# PS3604LRCF.net
KiCad netlist of a schematic drawn in Altium Designer
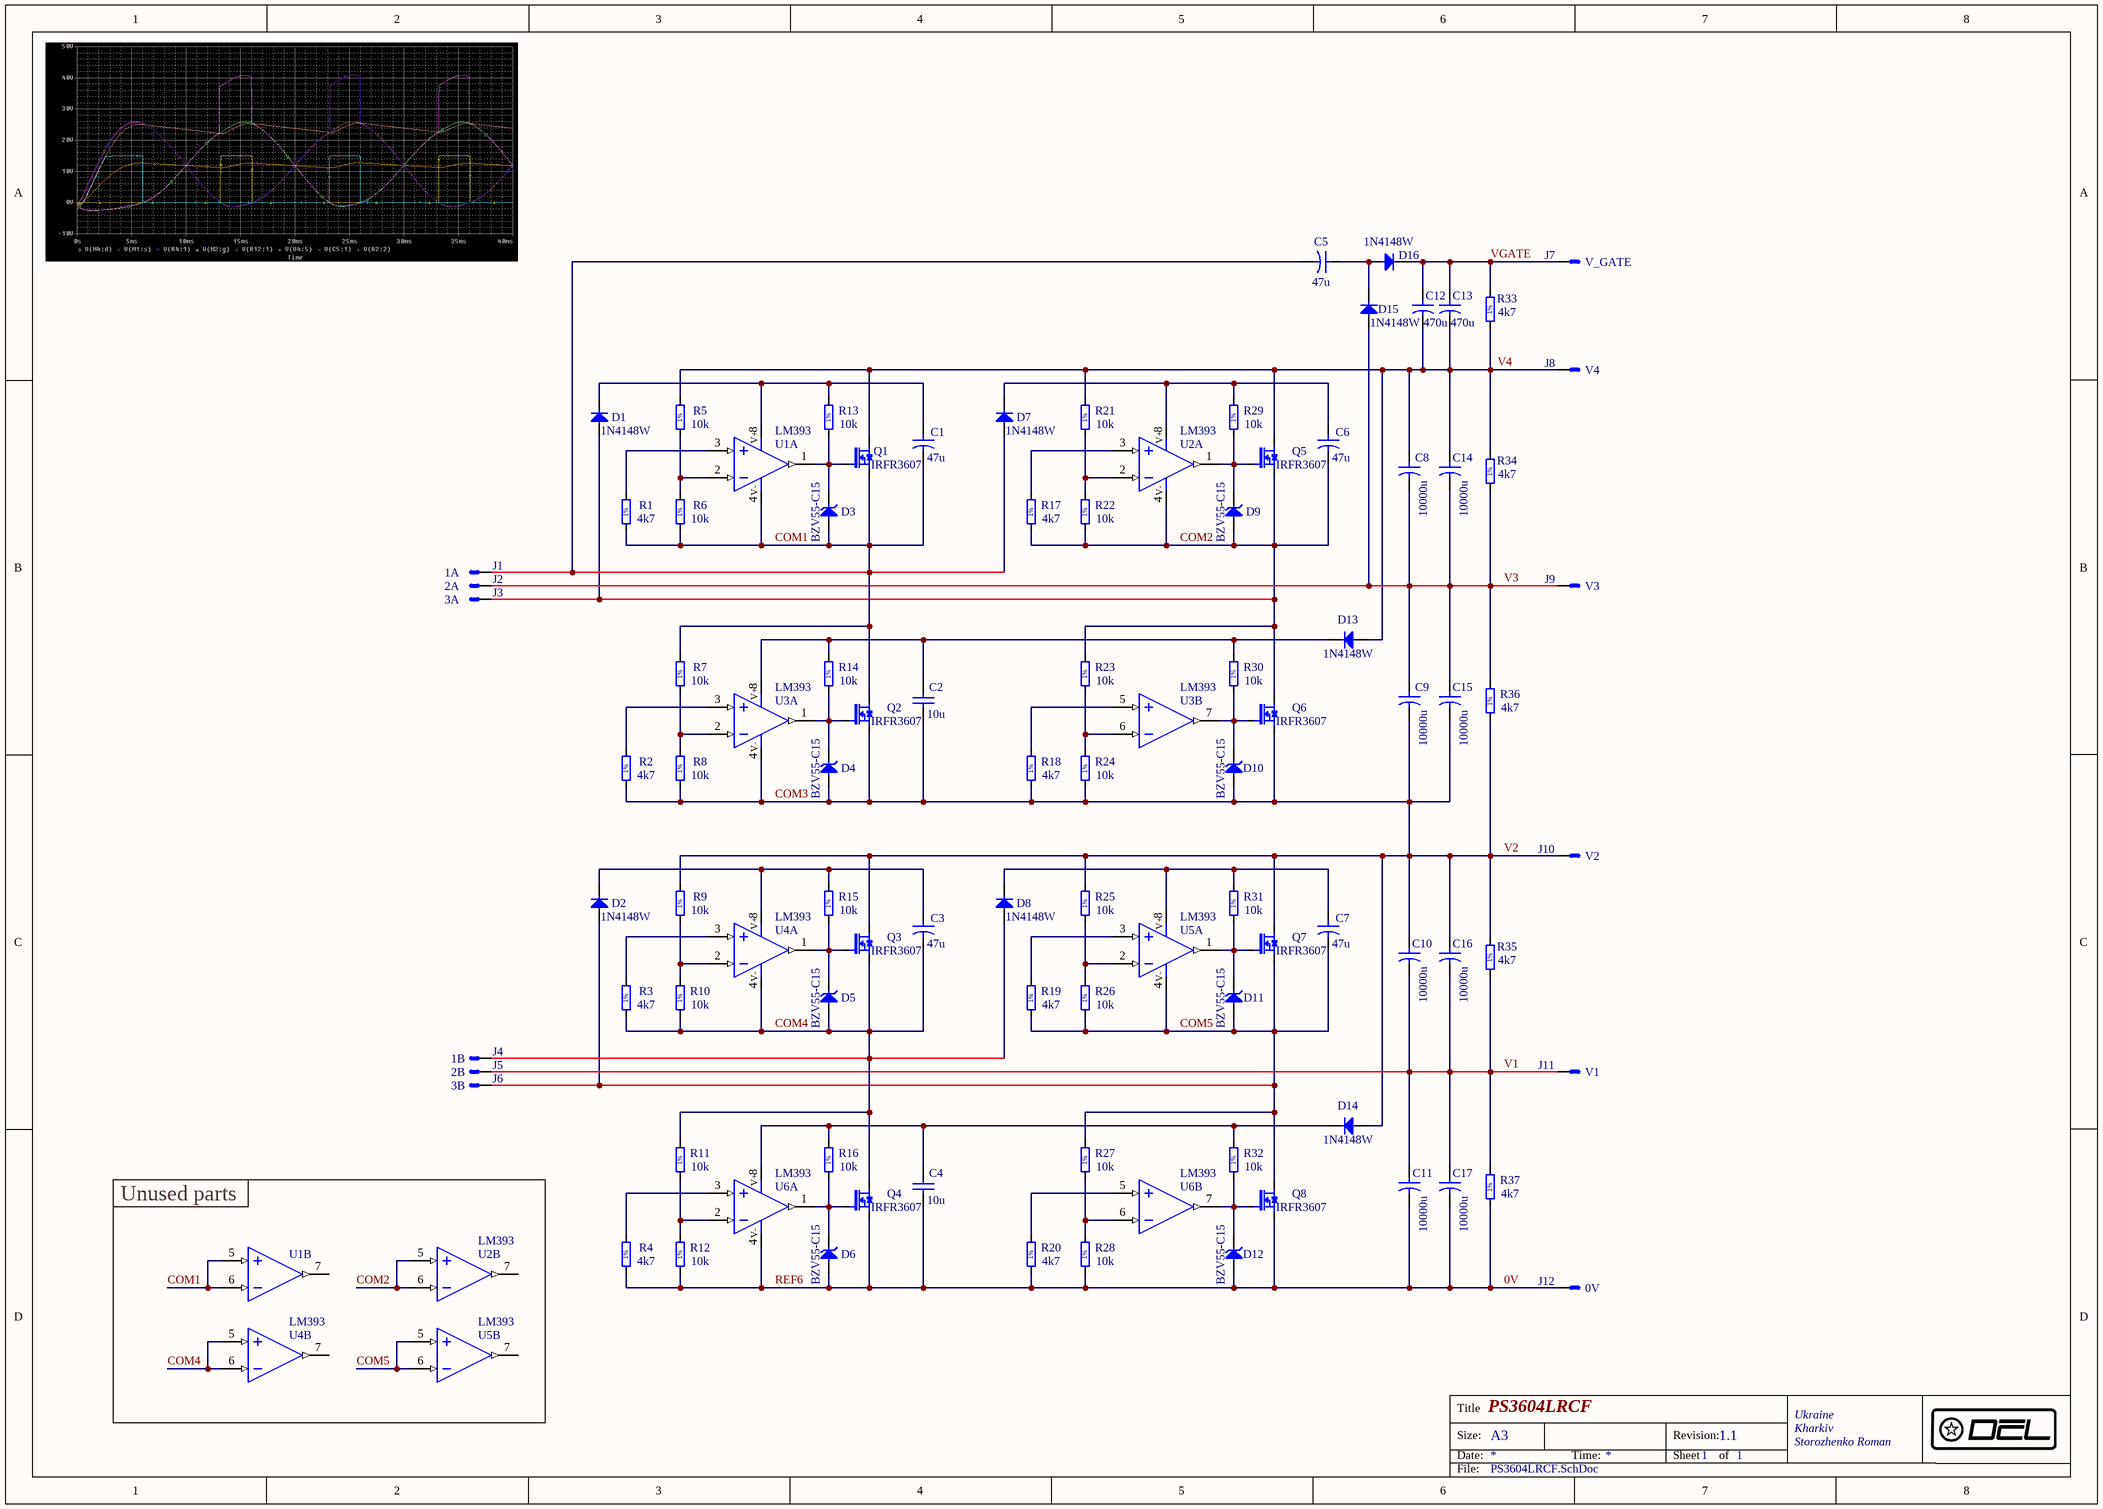
[diagram p0: PS3604LRCF.SchDoc]

(export (version "E")
  (design (tool "Eeschema 10.0.6"))
  (components
    (comp (ref "C1")
      (value "47u")
      (footprint "CAPPR250-630X1120")
      (description "Polarised capacitor")
      (fields
        (field (name "PART NUMBER") "CAER_47UF_50V_20%_EXR470M50B")
        (field (name "VOLTAGE") "50V")
        (field (name "AUTHOR") "DEL")
      )
      (libsource (lib "Capacitors") (part "Capacitor - polarized"))
    )
    (comp (ref "C2")
      (value "10u")
      (footprint "CAPC2012X135N")
      (description "Non-polarised capacitor")
      (fields
        (field (name "PART NUMBER") "CC0805_10UF_16V_10%_X7R")
        (field (name "VOLTAGE") "16V")
        (field (name "AUTHOR") "ELMAN")
      )
      (libsource (lib "Capacitors") (part "Capacitor - non polarized"))
    )
    (comp (ref "C3")
      (value "47u")
      (footprint "CAPPR250-630X1120")
      (description "Polarised capacitor")
      (fields
        (field (name "PART NUMBER") "CAER_47UF_50V_20%_EXR470M50B")
        (field (name "VOLTAGE") "50V")
        (field (name "AUTHOR") "DEL")
      )
      (libsource (lib "Capacitors") (part "Capacitor - polarized"))
    )
    (comp (ref "C4")
      (value "10u")
      (footprint "CAPC2012X135N")
      (description "Non-polarised capacitor")
      (fields
        (field (name "PART NUMBER") "CC0805_10UF_16V_10%_X7R")
        (field (name "VOLTAGE") "16V")
        (field (name "AUTHOR") "ELMAN")
      )
      (libsource (lib "Capacitors") (part "Capacitor - non polarized"))
    )
    (comp (ref "C5")
      (value "47u")
      (footprint "CAPPR250-630X1120")
      (description "Polarised capacitor")
      (fields
        (field (name "PART NUMBER") "CAER_47UF_50V_20%_EXR470M50B")
        (field (name "VOLTAGE") "50V")
        (field (name "AUTHOR") "DEL")
      )
      (libsource (lib "Capacitors") (part "Capacitor - polarized"))
    )
    (comp (ref "C6")
      (value "47u")
      (footprint "CAPPR250-630X1120")
      (description "Polarised capacitor")
      (fields
        (field (name "PART NUMBER") "CAER_47UF_50V_20%_EXR470M50B")
        (field (name "VOLTAGE") "50V")
        (field (name "AUTHOR") "DEL")
      )
      (libsource (lib "Capacitors") (part "Capacitor - polarized"))
    )
    (comp (ref "C7")
      (value "47u")
      (footprint "CAPPR250-630X1120")
      (description "Polarised capacitor")
      (fields
        (field (name "PART NUMBER") "CAER_47UF_50V_20%_EXR470M50B")
        (field (name "VOLTAGE") "50V")
        (field (name "AUTHOR") "DEL")
      )
      (libsource (lib "Capacitors") (part "Capacitor - polarized"))
    )
    (comp (ref "C8")
      (value "10000u")
      (footprint "CAPPR750-1850X3750")
      (description "Polarised capacitor")
      (fields
        (field (name "PART NUMBER") "CAER_10000UF_16V_20%_EXR103M16B")
        (field (name "VOLTAGE") "16V")
        (field (name "AUTHOR") "DEL")
      )
      (libsource (lib "Capacitors") (part "Capacitor - polarized"))
    )
    (comp (ref "C9")
      (value "10000u")
      (footprint "CAPPR750-1850X3750")
      (description "Polarised capacitor")
      (fields
        (field (name "PART NUMBER") "CAER_10000UF_16V_20%_EXR103M16B")
        (field (name "VOLTAGE") "16V")
        (field (name "AUTHOR") "DEL")
      )
      (libsource (lib "Capacitors") (part "Capacitor - polarized"))
    )
    (comp (ref "C10")
      (value "10000u")
      (footprint "CAPPR750-1850X3750")
      (description "Polarised capacitor")
      (fields
        (field (name "PART NUMBER") "CAER_10000UF_16V_20%_EXR103M16B")
        (field (name "VOLTAGE") "16V")
        (field (name "AUTHOR") "DEL")
      )
      (libsource (lib "Capacitors") (part "Capacitor - polarized"))
    )
    (comp (ref "C11")
      (value "10000u")
      (footprint "CAPPR750-1850X3750")
      (description "Polarised capacitor")
      (fields
        (field (name "PART NUMBER") "CAER_10000UF_16V_20%_EXR103M16B")
        (field (name "VOLTAGE") "16V")
        (field (name "AUTHOR") "DEL")
      )
      (libsource (lib "Capacitors") (part "Capacitor - polarized"))
    )
    (comp (ref "C12")
      (value "470u")
      (footprint "CAPPR500-1050X2200")
      (description "Polarised capacitor")
      (fields
        (field (name "PART NUMBER") "CAER_470UF_35V_20%_EXR471M35B")
        (field (name "VOLTAGE") "36V")
        (field (name "AUTHOR") "DEL")
      )
      (libsource (lib "Capacitors") (part "Capacitor - polarized"))
    )
    (comp (ref "C13")
      (value "470u")
      (footprint "CAPPR500-1050X2200")
      (description "Polarised capacitor")
      (fields
        (field (name "PART NUMBER") "CAER_470UF_35V_20%_EXR471M35B")
        (field (name "VOLTAGE") "36V")
        (field (name "AUTHOR") "DEL")
      )
      (libsource (lib "Capacitors") (part "Capacitor - polarized"))
    )
    (comp (ref "C14")
      (value "10000u")
      (footprint "CAPPR750-1850X3750")
      (description "Polarised capacitor")
      (fields
        (field (name "PART NUMBER") "CAER_10000UF_16V_20%_EXR103M16B")
        (field (name "VOLTAGE") "16V")
        (field (name "AUTHOR") "DEL")
      )
      (libsource (lib "Capacitors") (part "Capacitor - polarized"))
    )
    (comp (ref "C15")
      (value "10000u")
      (footprint "CAPPR750-1850X3750")
      (description "Polarised capacitor")
      (fields
        (field (name "PART NUMBER") "CAER_10000UF_16V_20%_EXR103M16B")
        (field (name "VOLTAGE") "16V")
        (field (name "AUTHOR") "DEL")
      )
      (libsource (lib "Capacitors") (part "Capacitor - polarized"))
    )
    (comp (ref "C16")
      (value "10000u")
      (footprint "CAPPR750-1850X3750")
      (description "Polarised capacitor")
      (fields
        (field (name "PART NUMBER") "CAER_10000UF_16V_20%_EXR103M16B")
        (field (name "VOLTAGE") "16V")
        (field (name "AUTHOR") "DEL")
      )
      (libsource (lib "Capacitors") (part "Capacitor - polarized"))
    )
    (comp (ref "C17")
      (value "10000u")
      (footprint "CAPPR750-1850X3750")
      (description "Polarised capacitor")
      (fields
        (field (name "PART NUMBER") "CAER_10000UF_16V_20%_EXR103M16B")
        (field (name "VOLTAGE") "16V")
        (field (name "AUTHOR") "DEL")
      )
      (libsource (lib "Capacitors") (part "Capacitor - polarized"))
    )
    (comp (ref "D1")
      (value "1N4148W")
      (footprint "SOD3715X145N")
      (description "Diode")
      (fields (field (name "VOLTAGE") "75V") (field (name "POWER") "150mA") (field (name "AUTHOR") "DEL"))
      (libsource (lib "ICs And Semiconductors") (part "Diode"))
    )
    (comp (ref "D2")
      (value "1N4148W")
      (footprint "SOD3715X145N")
      (description "Diode")
      (fields (field (name "VOLTAGE") "75V") (field (name "POWER") "150mA") (field (name "AUTHOR") "DEL"))
      (libsource (lib "ICs And Semiconductors") (part "Diode"))
    )
    (comp (ref "D3")
      (value "BZV55-C15")
      (footprint "DIOMELF3515N")
      (description "Zener Diode")
      (fields
        (field (name "VOLTAGE") "15V")
        (field (name "POWER") "500mW")
        (field (name "AUTHOR") "CERN DEM JLC")
      )
      (libsource (lib "ICs And Semiconductors") (part "Diode Zener"))
    )
    (comp (ref "D4")
      (value "BZV55-C15")
      (footprint "DIOMELF3515N")
      (description "Zener Diode")
      (fields
        (field (name "VOLTAGE") "15V")
        (field (name "POWER") "500mW")
        (field (name "AUTHOR") "CERN DEM JLC")
      )
      (libsource (lib "ICs And Semiconductors") (part "Diode Zener"))
    )
    (comp (ref "D5")
      (value "BZV55-C15")
      (footprint "DIOMELF3515N")
      (description "Zener Diode")
      (fields
        (field (name "VOLTAGE") "15V")
        (field (name "POWER") "500mW")
        (field (name "AUTHOR") "CERN DEM JLC")
      )
      (libsource (lib "ICs And Semiconductors") (part "Diode Zener"))
    )
    (comp (ref "D6")
      (value "BZV55-C15")
      (footprint "DIOMELF3515N")
      (description "Zener Diode")
      (fields
        (field (name "VOLTAGE") "15V")
        (field (name "POWER") "500mW")
        (field (name "AUTHOR") "CERN DEM JLC")
      )
      (libsource (lib "ICs And Semiconductors") (part "Diode Zener"))
    )
    (comp (ref "D7")
      (value "1N4148W")
      (footprint "SOD3715X145N")
      (description "Diode")
      (fields (field (name "VOLTAGE") "75V") (field (name "POWER") "150mA") (field (name "AUTHOR") "DEL"))
      (libsource (lib "ICs And Semiconductors") (part "Diode"))
    )
    (comp (ref "D8")
      (value "1N4148W")
      (footprint "SOD3715X145N")
      (description "Diode")
      (fields (field (name "VOLTAGE") "75V") (field (name "POWER") "150mA") (field (name "AUTHOR") "DEL"))
      (libsource (lib "ICs And Semiconductors") (part "Diode"))
    )
    (comp (ref "D9")
      (value "BZV55-C15")
      (footprint "DIOMELF3515N")
      (description "Zener Diode")
      (fields
        (field (name "VOLTAGE") "15V")
        (field (name "POWER") "500mW")
        (field (name "AUTHOR") "CERN DEM JLC")
      )
      (libsource (lib "ICs And Semiconductors") (part "Diode Zener"))
    )
    (comp (ref "D10")
      (value "BZV55-C15")
      (footprint "DIOMELF3515N")
      (description "Zener Diode")
      (fields
        (field (name "VOLTAGE") "15V")
        (field (name "POWER") "500mW")
        (field (name "AUTHOR") "CERN DEM JLC")
      )
      (libsource (lib "ICs And Semiconductors") (part "Diode Zener"))
    )
    (comp (ref "D11")
      (value "BZV55-C15")
      (footprint "DIOMELF3515N")
      (description "Zener Diode")
      (fields
        (field (name "VOLTAGE") "15V")
        (field (name "POWER") "500mW")
        (field (name "AUTHOR") "CERN DEM JLC")
      )
      (libsource (lib "ICs And Semiconductors") (part "Diode Zener"))
    )
    (comp (ref "D12")
      (value "BZV55-C15")
      (footprint "DIOMELF3515N")
      (description "Zener Diode")
      (fields
        (field (name "VOLTAGE") "15V")
        (field (name "POWER") "500mW")
        (field (name "AUTHOR") "CERN DEM JLC")
      )
      (libsource (lib "ICs And Semiconductors") (part "Diode Zener"))
    )
    (comp (ref "D13")
      (value "1N4148W")
      (footprint "SOD3715X145N")
      (description "Diode")
      (fields (field (name "VOLTAGE") "75V") (field (name "POWER") "150mA") (field (name "AUTHOR") "DEL"))
      (libsource (lib "ICs And Semiconductors") (part "Diode"))
    )
    (comp (ref "D14")
      (value "1N4148W")
      (footprint "SOD3715X145N")
      (description "Diode")
      (fields (field (name "VOLTAGE") "75V") (field (name "POWER") "150mA") (field (name "AUTHOR") "DEL"))
      (libsource (lib "ICs And Semiconductors") (part "Diode"))
    )
    (comp (ref "D15")
      (value "1N4148W")
      (footprint "SOD3715X145N")
      (description "Diode")
      (fields (field (name "VOLTAGE") "75V") (field (name "POWER") "150mA") (field (name "AUTHOR") "DEL"))
      (libsource (lib "ICs And Semiconductors") (part "Diode"))
    )
    (comp (ref "D16")
      (value "1N4148W")
      (footprint "SOD3715X145N")
      (description "Diode")
      (fields (field (name "VOLTAGE") "75V") (field (name "POWER") "150mA") (field (name "AUTHOR") "DEL"))
      (libsource (lib "ICs And Semiconductors") (part "Diode"))
    )
    (comp (ref "J1")
      (value "Quixon™")
      (footprint "MOLEX_19_70_54203")
      (description "Single Pin Male")
      (fields
        (field (name "PART NUMBER") "MOLEX_19_70_54203")
        (field (name "MANUFACTURER") "MOLEX")
        (field (name "AUTHOR") "DEL")
      )
      (libsource (lib "Connectors") (part "Single Pin Male"))
    )
    (comp (ref "J2")
      (value "Quixon™")
      (footprint "MOLEX_19_70_54203")
      (description "Single Pin Male")
      (fields
        (field (name "PART NUMBER") "MOLEX_19_70_54203")
        (field (name "MANUFACTURER") "MOLEX")
        (field (name "AUTHOR") "DEL")
      )
      (libsource (lib "Connectors") (part "Single Pin Male"))
    )
    (comp (ref "J3")
      (value "Quixon™")
      (footprint "MOLEX_19_70_54203")
      (description "Single Pin Male")
      (fields
        (field (name "PART NUMBER") "MOLEX_19_70_54203")
        (field (name "MANUFACTURER") "MOLEX")
        (field (name "AUTHOR") "DEL")
      )
      (libsource (lib "Connectors") (part "Single Pin Male"))
    )
    (comp (ref "J4")
      (value "Quixon™")
      (footprint "MOLEX_19_70_54203")
      (description "Single Pin Male")
      (fields
        (field (name "PART NUMBER") "MOLEX_19_70_54203")
        (field (name "MANUFACTURER") "MOLEX")
        (field (name "AUTHOR") "DEL")
      )
      (libsource (lib "Connectors") (part "Single Pin Male"))
    )
    (comp (ref "J5")
      (value "Quixon™")
      (footprint "MOLEX_19_70_54203")
      (description "Single Pin Male")
      (fields
        (field (name "PART NUMBER") "MOLEX_19_70_54203")
        (field (name "MANUFACTURER") "MOLEX")
        (field (name "AUTHOR") "DEL")
      )
      (libsource (lib "Connectors") (part "Single Pin Male"))
    )
    (comp (ref "J6")
      (value "Quixon™")
      (footprint "MOLEX_19_70_54203")
      (description "Single Pin Male")
      (fields
        (field (name "PART NUMBER") "MOLEX_19_70_54203")
        (field (name "MANUFACTURER") "MOLEX")
        (field (name "AUTHOR") "DEL")
      )
      (libsource (lib "Connectors") (part "Single Pin Male"))
    )
    (comp (ref "J7")
      (value "Quixon™")
      (footprint "MOLEX_19_70_54203")
      (description "Single Pin Male")
      (fields
        (field (name "PART NUMBER") "MOLEX_19_70_54203")
        (field (name "MANUFACTURER") "MOLEX")
        (field (name "AUTHOR") "DEL")
      )
      (libsource (lib "Connectors") (part "Single Pin Male"))
    )
    (comp (ref "J8")
      (value "Quixon™")
      (footprint "MOLEX_19_70_54203")
      (description "Single Pin Male")
      (fields
        (field (name "PART NUMBER") "MOLEX_19_70_54203")
        (field (name "MANUFACTURER") "MOLEX")
        (field (name "AUTHOR") "DEL")
      )
      (libsource (lib "Connectors") (part "Single Pin Male"))
    )
    (comp (ref "J9")
      (value "Quixon™")
      (footprint "MOLEX_19_70_54203")
      (description "Single Pin Male")
      (fields
        (field (name "PART NUMBER") "MOLEX_19_70_54203")
        (field (name "MANUFACTURER") "MOLEX")
        (field (name "AUTHOR") "DEL")
      )
      (libsource (lib "Connectors") (part "Single Pin Male"))
    )
    (comp (ref "J10")
      (value "Quixon™")
      (footprint "MOLEX_19_70_54203")
      (description "Single Pin Male")
      (fields
        (field (name "PART NUMBER") "MOLEX_19_70_54203")
        (field (name "MANUFACTURER") "MOLEX")
        (field (name "AUTHOR") "DEL")
      )
      (libsource (lib "Connectors") (part "Single Pin Male"))
    )
    (comp (ref "J11")
      (value "Quixon™")
      (footprint "MOLEX_19_70_54203")
      (description "Single Pin Male")
      (fields
        (field (name "PART NUMBER") "MOLEX_19_70_54203")
        (field (name "MANUFACTURER") "MOLEX")
        (field (name "AUTHOR") "DEL")
      )
      (libsource (lib "Connectors") (part "Single Pin Male"))
    )
    (comp (ref "J12")
      (value "Quixon™")
      (footprint "MOLEX_19_70_54203")
      (description "Single Pin Male")
      (fields
        (field (name "PART NUMBER") "MOLEX_19_70_54203")
        (field (name "MANUFACTURER") "MOLEX")
        (field (name "AUTHOR") "DEL")
      )
      (libsource (lib "Connectors") (part "Single Pin Male"))
    )
    (comp (ref "Q1")
      (value "IRFR3607")
      (footprint "TO228P991X239-3N-R546X521")
      (description "N-CHANNEL MOSFET WITH DIODE")
      (fields
        (field (name "PART NUMBER") "IRFR3607PbF")
        (field (name "MANUFACTURER") "INTERNATIONAL RECTIFIER")
        (field (name "AUTHOR") "DEL")
      )
      (libsource (lib "ICs And Semiconductors") (part "N-MOSFET-D 1G 2S 3D"))
    )
    (comp (ref "Q2")
      (value "IRFR3607")
      (footprint "TO228P991X239-3N-R546X521")
      (description "N-CHANNEL MOSFET WITH DIODE")
      (fields
        (field (name "PART NUMBER") "IRFR3607PbF")
        (field (name "MANUFACTURER") "INTERNATIONAL RECTIFIER")
        (field (name "AUTHOR") "DEL")
      )
      (libsource (lib "ICs And Semiconductors") (part "N-MOSFET-D 1G 2S 3D"))
    )
    (comp (ref "Q3")
      (value "IRFR3607")
      (footprint "TO228P991X239-3N-R546X521")
      (description "N-CHANNEL MOSFET WITH DIODE")
      (fields
        (field (name "PART NUMBER") "IRFR3607PbF")
        (field (name "MANUFACTURER") "INTERNATIONAL RECTIFIER")
        (field (name "AUTHOR") "DEL")
      )
      (libsource (lib "ICs And Semiconductors") (part "N-MOSFET-D 1G 2S 3D"))
    )
    (comp (ref "Q4")
      (value "IRFR3607")
      (footprint "TO228P991X239-3N-R546X521")
      (description "N-CHANNEL MOSFET WITH DIODE")
      (fields
        (field (name "PART NUMBER") "IRFR3607PbF")
        (field (name "MANUFACTURER") "INTERNATIONAL RECTIFIER")
        (field (name "AUTHOR") "DEL")
      )
      (libsource (lib "ICs And Semiconductors") (part "N-MOSFET-D 1G 2S 3D"))
    )
    (comp (ref "Q5")
      (value "IRFR3607")
      (footprint "TO228P991X239-3N-R546X521")
      (description "N-CHANNEL MOSFET WITH DIODE")
      (fields
        (field (name "PART NUMBER") "IRFR3607PbF")
        (field (name "MANUFACTURER") "INTERNATIONAL RECTIFIER")
        (field (name "AUTHOR") "DEL")
      )
      (libsource (lib "ICs And Semiconductors") (part "N-MOSFET-D 1G 2S 3D"))
    )
    (comp (ref "Q6")
      (value "IRFR3607")
      (footprint "TO228P991X239-3N-R546X521")
      (description "N-CHANNEL MOSFET WITH DIODE")
      (fields
        (field (name "PART NUMBER") "IRFR3607PbF")
        (field (name "MANUFACTURER") "INTERNATIONAL RECTIFIER")
        (field (name "AUTHOR") "DEL")
      )
      (libsource (lib "ICs And Semiconductors") (part "N-MOSFET-D 1G 2S 3D"))
    )
    (comp (ref "Q7")
      (value "IRFR3607")
      (footprint "TO228P991X239-3N-R546X521")
      (description "N-CHANNEL MOSFET WITH DIODE")
      (fields
        (field (name "PART NUMBER") "IRFR3607PbF")
        (field (name "MANUFACTURER") "INTERNATIONAL RECTIFIER")
        (field (name "AUTHOR") "DEL")
      )
      (libsource (lib "ICs And Semiconductors") (part "N-MOSFET-D 1G 2S 3D"))
    )
    (comp (ref "Q8")
      (value "IRFR3607")
      (footprint "TO228P991X239-3N-R546X521")
      (description "N-CHANNEL MOSFET WITH DIODE")
      (fields
        (field (name "PART NUMBER") "IRFR3607PbF")
        (field (name "MANUFACTURER") "INTERNATIONAL RECTIFIER")
        (field (name "AUTHOR") "DEL")
      )
      (libsource (lib "ICs And Semiconductors") (part "N-MOSFET-D 1G 2S 3D"))
    )
    (comp (ref "R1")
      (value "4k7")
      (footprint "RESC1608X55N")
      (description "Resistor - 1%")
      (fields
        (field (name "PART NUMBER") "R0603_4K7_1%_0.1W_100PPM")
        (field (name "POWER") "0.1W")
        (field (name "AUTHOR") "CERN DEM JLC")
      )
      (libsource (lib "Resistors") (part "Resistor - 1%"))
    )
    (comp (ref "R2")
      (value "4k7")
      (footprint "RESC1608X55N")
      (description "Resistor - 1%")
      (fields
        (field (name "PART NUMBER") "R0603_4K7_1%_0.1W_100PPM")
        (field (name "POWER") "0.1W")
        (field (name "AUTHOR") "CERN DEM JLC")
      )
      (libsource (lib "Resistors") (part "Resistor - 1%"))
    )
    (comp (ref "R3")
      (value "4k7")
      (footprint "RESC1608X55N")
      (description "Resistor - 1%")
      (fields
        (field (name "PART NUMBER") "R0603_4K7_1%_0.1W_100PPM")
        (field (name "POWER") "0.1W")
        (field (name "AUTHOR") "CERN DEM JLC")
      )
      (libsource (lib "Resistors") (part "Resistor - 1%"))
    )
    (comp (ref "R4")
      (value "4k7")
      (footprint "RESC1608X55N")
      (description "Resistor - 1%")
      (fields
        (field (name "PART NUMBER") "R0603_4K7_1%_0.1W_100PPM")
        (field (name "POWER") "0.1W")
        (field (name "AUTHOR") "CERN DEM JLC")
      )
      (libsource (lib "Resistors") (part "Resistor - 1%"))
    )
    (comp (ref "R5")
      (value "10k")
      (footprint "RESC1608X55N")
      (description "Resistor - 1%")
      (fields
        (field (name "PART NUMBER") "R0603_10K_1%_0.1W_100PPM")
        (field (name "POWER") "0.1W")
        (field (name "AUTHOR") "CERN DEM JLC")
      )
      (libsource (lib "Resistors") (part "Resistor - 1%"))
    )
    (comp (ref "R6")
      (value "10k")
      (footprint "RESC1608X55N")
      (description "Resistor - 1%")
      (fields
        (field (name "PART NUMBER") "R0603_10K_1%_0.1W_100PPM")
        (field (name "POWER") "0.1W")
        (field (name "AUTHOR") "CERN DEM JLC")
      )
      (libsource (lib "Resistors") (part "Resistor - 1%"))
    )
    (comp (ref "R7")
      (value "10k")
      (footprint "RESC1608X55N")
      (description "Resistor - 1%")
      (fields
        (field (name "PART NUMBER") "R0603_10K_1%_0.1W_100PPM")
        (field (name "POWER") "0.1W")
        (field (name "AUTHOR") "CERN DEM JLC")
      )
      (libsource (lib "Resistors") (part "Resistor - 1%"))
    )
    (comp (ref "R8")
      (value "10k")
      (footprint "RESC1608X55N")
      (description "Resistor - 1%")
      (fields
        (field (name "PART NUMBER") "R0603_10K_1%_0.1W_100PPM")
        (field (name "POWER") "0.1W")
        (field (name "AUTHOR") "CERN DEM JLC")
      )
      (libsource (lib "Resistors") (part "Resistor - 1%"))
    )
    (comp (ref "R9")
      (value "10k")
      (footprint "RESC1608X55N")
      (description "Resistor - 1%")
      (fields
        (field (name "PART NUMBER") "R0603_10K_1%_0.1W_100PPM")
        (field (name "POWER") "0.1W")
        (field (name "AUTHOR") "CERN DEM JLC")
      )
      (libsource (lib "Resistors") (part "Resistor - 1%"))
    )
    (comp (ref "R10")
      (value "10k")
      (footprint "RESC1608X55N")
      (description "Resistor - 1%")
      (fields
        (field (name "PART NUMBER") "R0603_10K_1%_0.1W_100PPM")
        (field (name "POWER") "0.1W")
        (field (name "AUTHOR") "CERN DEM JLC")
      )
      (libsource (lib "Resistors") (part "Resistor - 1%"))
    )
    (comp (ref "R11")
      (value "10k")
      (footprint "RESC1608X55N")
      (description "Resistor - 1%")
      (fields
        (field (name "PART NUMBER") "R0603_10K_1%_0.1W_100PPM")
        (field (name "POWER") "0.1W")
        (field (name "AUTHOR") "CERN DEM JLC")
      )
      (libsource (lib "Resistors") (part "Resistor - 1%"))
    )
    (comp (ref "R12")
      (value "10k")
      (footprint "RESC1608X55N")
      (description "Resistor - 1%")
      (fields
        (field (name "PART NUMBER") "R0603_10K_1%_0.1W_100PPM")
        (field (name "POWER") "0.1W")
        (field (name "AUTHOR") "CERN DEM JLC")
      )
      (libsource (lib "Resistors") (part "Resistor - 1%"))
    )
    (comp (ref "R13")
      (value "10k")
      (footprint "RESC1608X55N")
      (description "Resistor - 1%")
      (fields
        (field (name "PART NUMBER") "R0603_10K_1%_0.1W_100PPM")
        (field (name "POWER") "0.1W")
        (field (name "AUTHOR") "CERN DEM JLC")
      )
      (libsource (lib "Resistors") (part "Resistor - 1%"))
    )
    (comp (ref "R14")
      (value "10k")
      (footprint "RESC1608X55N")
      (description "Resistor - 1%")
      (fields
        (field (name "PART NUMBER") "R0603_10K_1%_0.1W_100PPM")
        (field (name "POWER") "0.1W")
        (field (name "AUTHOR") "CERN DEM JLC")
      )
      (libsource (lib "Resistors") (part "Resistor - 1%"))
    )
    (comp (ref "R15")
      (value "10k")
      (footprint "RESC1608X55N")
      (description "Resistor - 1%")
      (fields
        (field (name "PART NUMBER") "R0603_10K_1%_0.1W_100PPM")
        (field (name "POWER") "0.1W")
        (field (name "AUTHOR") "CERN DEM JLC")
      )
      (libsource (lib "Resistors") (part "Resistor - 1%"))
    )
    (comp (ref "R16")
      (value "10k")
      (footprint "RESC1608X55N")
      (description "Resistor - 1%")
      (fields
        (field (name "PART NUMBER") "R0603_10K_1%_0.1W_100PPM")
        (field (name "POWER") "0.1W")
        (field (name "AUTHOR") "CERN DEM JLC")
      )
      (libsource (lib "Resistors") (part "Resistor - 1%"))
    )
    (comp (ref "R17")
      (value "4k7")
      (footprint "RESC1608X55N")
      (description "Resistor - 1%")
      (fields
        (field (name "PART NUMBER") "R0603_4K7_1%_0.1W_100PPM")
        (field (name "POWER") "0.1W")
        (field (name "AUTHOR") "CERN DEM JLC")
      )
      (libsource (lib "Resistors") (part "Resistor - 1%"))
    )
    (comp (ref "R18")
      (value "4k7")
      (footprint "RESC1608X55N")
      (description "Resistor - 1%")
      (fields
        (field (name "PART NUMBER") "R0603_4K7_1%_0.1W_100PPM")
        (field (name "POWER") "0.1W")
        (field (name "AUTHOR") "CERN DEM JLC")
      )
      (libsource (lib "Resistors") (part "Resistor - 1%"))
    )
    (comp (ref "R19")
      (value "4k7")
      (footprint "RESC1608X55N")
      (description "Resistor - 1%")
      (fields
        (field (name "PART NUMBER") "R0603_4K7_1%_0.1W_100PPM")
        (field (name "POWER") "0.1W")
        (field (name "AUTHOR") "CERN DEM JLC")
      )
      (libsource (lib "Resistors") (part "Resistor - 1%"))
    )
    (comp (ref "R20")
      (value "4k7")
      (footprint "RESC1608X55N")
      (description "Resistor - 1%")
      (fields
        (field (name "PART NUMBER") "R0603_4K7_1%_0.1W_100PPM")
        (field (name "POWER") "0.1W")
        (field (name "AUTHOR") "CERN DEM JLC")
      )
      (libsource (lib "Resistors") (part "Resistor - 1%"))
    )
    (comp (ref "R21")
      (value "10k")
      (footprint "RESC1608X55N")
      (description "Resistor - 1%")
      (fields
        (field (name "PART NUMBER") "R0603_10K_1%_0.1W_100PPM")
        (field (name "POWER") "0.1W")
        (field (name "AUTHOR") "CERN DEM JLC")
      )
      (libsource (lib "Resistors") (part "Resistor - 1%"))
    )
    (comp (ref "R22")
      (value "10k")
      (footprint "RESC1608X55N")
      (description "Resistor - 1%")
      (fields
        (field (name "PART NUMBER") "R0603_10K_1%_0.1W_100PPM")
        (field (name "POWER") "0.1W")
        (field (name "AUTHOR") "CERN DEM JLC")
      )
      (libsource (lib "Resistors") (part "Resistor - 1%"))
    )
    (comp (ref "R23")
      (value "10k")
      (footprint "RESC1608X55N")
      (description "Resistor - 1%")
      (fields
        (field (name "PART NUMBER") "R0603_10K_1%_0.1W_100PPM")
        (field (name "POWER") "0.1W")
        (field (name "AUTHOR") "CERN DEM JLC")
      )
      (libsource (lib "Resistors") (part "Resistor - 1%"))
    )
    (comp (ref "R24")
      (value "10k")
      (footprint "RESC1608X55N")
      (description "Resistor - 1%")
      (fields
        (field (name "PART NUMBER") "R0603_10K_1%_0.1W_100PPM")
        (field (name "POWER") "0.1W")
        (field (name "AUTHOR") "CERN DEM JLC")
      )
      (libsource (lib "Resistors") (part "Resistor - 1%"))
    )
    (comp (ref "R25")
      (value "10k")
      (footprint "RESC1608X55N")
      (description "Resistor - 1%")
      (fields
        (field (name "PART NUMBER") "R0603_10K_1%_0.1W_100PPM")
        (field (name "POWER") "0.1W")
        (field (name "AUTHOR") "CERN DEM JLC")
      )
      (libsource (lib "Resistors") (part "Resistor - 1%"))
    )
    (comp (ref "R26")
      (value "10k")
      (footprint "RESC1608X55N")
      (description "Resistor - 1%")
      (fields
        (field (name "PART NUMBER") "R0603_10K_1%_0.1W_100PPM")
        (field (name "POWER") "0.1W")
        (field (name "AUTHOR") "CERN DEM JLC")
      )
      (libsource (lib "Resistors") (part "Resistor - 1%"))
    )
    (comp (ref "R27")
      (value "10k")
      (footprint "RESC1608X55N")
      (description "Resistor - 1%")
      (fields
        (field (name "PART NUMBER") "R0603_10K_1%_0.1W_100PPM")
        (field (name "POWER") "0.1W")
        (field (name "AUTHOR") "CERN DEM JLC")
      )
      (libsource (lib "Resistors") (part "Resistor - 1%"))
    )
    (comp (ref "R28")
      (value "10k")
      (footprint "RESC1608X55N")
      (description "Resistor - 1%")
      (fields
        (field (name "PART NUMBER") "R0603_10K_1%_0.1W_100PPM")
        (field (name "POWER") "0.1W")
        (field (name "AUTHOR") "CERN DEM JLC")
      )
      (libsource (lib "Resistors") (part "Resistor - 1%"))
    )
    (comp (ref "R29")
      (value "10k")
      (footprint "RESC1608X55N")
      (description "Resistor - 1%")
      (fields
        (field (name "PART NUMBER") "R0603_10K_1%_0.1W_100PPM")
        (field (name "POWER") "0.1W")
        (field (name "AUTHOR") "CERN DEM JLC")
      )
      (libsource (lib "Resistors") (part "Resistor - 1%"))
    )
    (comp (ref "R30")
      (value "10k")
      (footprint "RESC1608X55N")
      (description "Resistor - 1%")
      (fields
        (field (name "PART NUMBER") "R0603_10K_1%_0.1W_100PPM")
        (field (name "POWER") "0.1W")
        (field (name "AUTHOR") "CERN DEM JLC")
      )
      (libsource (lib "Resistors") (part "Resistor - 1%"))
    )
    (comp (ref "R31")
      (value "10k")
      (footprint "RESC1608X55N")
      (description "Resistor - 1%")
      (fields
        (field (name "PART NUMBER") "R0603_10K_1%_0.1W_100PPM")
        (field (name "POWER") "0.1W")
        (field (name "AUTHOR") "CERN DEM JLC")
      )
      (libsource (lib "Resistors") (part "Resistor - 1%"))
    )
    (comp (ref "R32")
      (value "10k")
      (footprint "RESC1608X55N")
      (description "Resistor - 1%")
      (fields
        (field (name "PART NUMBER") "R0603_10K_1%_0.1W_100PPM")
        (field (name "POWER") "0.1W")
        (field (name "AUTHOR") "CERN DEM JLC")
      )
      (libsource (lib "Resistors") (part "Resistor - 1%"))
    )
    (comp (ref "R33")
      (value "4k7")
      (footprint "RESC1608X55N")
      (description "Resistor - 1%")
      (fields
        (field (name "PART NUMBER") "R0603_4K7_1%_0.1W_100PPM")
        (field (name "POWER") "0.1W")
        (field (name "AUTHOR") "CERN DEM JLC")
      )
      (libsource (lib "Resistors") (part "Resistor - 1%"))
    )
    (comp (ref "R34")
      (value "4k7")
      (footprint "RESC1608X55N")
      (description "Resistor - 1%")
      (fields
        (field (name "PART NUMBER") "R0603_4K7_1%_0.1W_100PPM")
        (field (name "POWER") "0.1W")
        (field (name "AUTHOR") "CERN DEM JLC")
      )
      (libsource (lib "Resistors") (part "Resistor - 1%"))
    )
    (comp (ref "R35")
      (value "4k7")
      (footprint "RESC1608X55N")
      (description "Resistor - 1%")
      (fields
        (field (name "PART NUMBER") "R0603_4K7_1%_0.1W_100PPM")
        (field (name "POWER") "0.1W")
        (field (name "AUTHOR") "CERN DEM JLC")
      )
      (libsource (lib "Resistors") (part "Resistor - 1%"))
    )
    (comp (ref "R36")
      (value "4k7")
      (footprint "RESC1608X55N")
      (description "Resistor - 1%")
      (fields
        (field (name "PART NUMBER") "R0603_4K7_1%_0.1W_100PPM")
        (field (name "POWER") "0.1W")
        (field (name "AUTHOR") "CERN DEM JLC")
      )
      (libsource (lib "Resistors") (part "Resistor - 1%"))
    )
    (comp (ref "R37")
      (value "4k7")
      (footprint "RESC1608X55N")
      (description "Resistor - 1%")
      (fields
        (field (name "PART NUMBER") "R0603_4K7_1%_0.1W_100PPM")
        (field (name "POWER") "0.1W")
        (field (name "AUTHOR") "CERN DEM JLC")
      )
      (libsource (lib "Resistors") (part "Resistor - 1%"))
    )
    (comp (ref "U1")
      (value "LM393M/NOPB")
      (footprint "SOIC127P600X175-8N")
      (description "Dual Operational Amplifier")
      (fields
        (field (name "MANUFACTURER") "NATIONAL SEMICONDUCTOR")
        (field (name "PART NUMBER") "LM393M/NOPB")
        (field (name "AUTHOR") "CERN DEM JLC")
      )
      (libsource (lib "ICs And Semiconductors") (part "Operational Amplifier x2 Type1"))
    )
    (comp (ref "U2")
      (value "LM393")
      (footprint "SOIC127P600X175-8N")
      (description "Dual Operational Amplifier")
      (fields
        (field (name "PART NUMBER") "LM393M/NOPB")
        (field (name "MANUFACTURER") "NATIONAL SEMICONDUCTOR")
        (field (name "AUTHOR") "CERN DEM JLC")
      )
      (libsource (lib "ICs And Semiconductors") (part "Operational Amplifier x2 Type1"))
    )
    (comp (ref "U3")
      (value "LM393")
      (footprint "SOIC127P600X175-8N")
      (description "Dual Operational Amplifier")
      (fields
        (field (name "PART NUMBER") "LM393M/NOPB")
        (field (name "MANUFACTURER") "NATIONAL SEMICONDUCTOR")
        (field (name "AUTHOR") "CERN DEM JLC")
      )
      (libsource (lib "ICs And Semiconductors") (part "Operational Amplifier x2 Type1"))
    )
    (comp (ref "U4")
      (value "LM393")
      (footprint "SOIC127P600X175-8N")
      (description "Dual Operational Amplifier")
      (fields
        (field (name "PART NUMBER") "LM393M/NOPB")
        (field (name "MANUFACTURER") "NATIONAL SEMICONDUCTOR")
        (field (name "AUTHOR") "CERN DEM JLC")
      )
      (libsource (lib "ICs And Semiconductors") (part "Operational Amplifier x2 Type1"))
    )
    (comp (ref "U5")
      (value "LM393")
      (footprint "SOIC127P600X175-8N")
      (description "Dual Operational Amplifier")
      (fields
        (field (name "PART NUMBER") "LM393M/NOPB")
        (field (name "MANUFACTURER") "NATIONAL SEMICONDUCTOR")
        (field (name "AUTHOR") "CERN DEM JLC")
      )
      (libsource (lib "ICs And Semiconductors") (part "Operational Amplifier x2 Type1"))
    )
    (comp (ref "U6")
      (value "LM393")
      (footprint "SOIC127P600X175-8N")
      (description "Dual Operational Amplifier")
      (fields
        (field (name "PART NUMBER") "LM393M/NOPB")
        (field (name "MANUFACTURER") "NATIONAL SEMICONDUCTOR")
        (field (name "AUTHOR") "CERN DEM JLC")
      )
      (libsource (lib "ICs And Semiconductors") (part "Operational Amplifier x2 Type1"))
    )
  )
  (nets
    (net (code "1") (name "/0V") (class "Default")
      (node (ref "C11") (pin "2") (pinfunction "2_2") (pintype "passive"))
      (node (ref "C17") (pin "2") (pinfunction "2_2") (pintype "passive"))
      (node (ref "C4") (pin "1") (pinfunction "1_1") (pintype "passive"))
      (node (ref "D12") (pin "2") (pinfunction "A_2") (pintype "passive"))
      (node (ref "D6") (pin "2") (pinfunction "A_2") (pintype "passive"))
      (node (ref "J12") (pin "1") (pinfunction "1_1") (pintype "bidirectional"))
      (node (ref "Q4") (pin "2") (pinfunction "S_2") (pintype "passive"))
      (node (ref "Q8") (pin "2") (pinfunction "S_2") (pintype "passive"))
      (node (ref "R12") (pin "1") (pinfunction "1_1") (pintype "passive"))
      (node (ref "R20") (pin "1") (pinfunction "1_1") (pintype "passive"))
      (node (ref "R28") (pin "1") (pinfunction "1_1") (pintype "passive"))
      (node (ref "R37") (pin "1") (pinfunction "1_1") (pintype "passive"))
      (node (ref "R4") (pin "1") (pinfunction "1_1") (pintype "passive"))
      (node (ref "U6") (pin "4") (pinfunction "V-_4") (pintype "power_in"))
    )
    (net (code "2") (name "/COM1") (class "Default")
      (node (ref "C1") (pin "2") (pinfunction "2_2") (pintype "passive"))
      (node (ref "C5") (pin "2") (pinfunction "2_2") (pintype "passive"))
      (node (ref "D3") (pin "2") (pinfunction "A_2") (pintype "passive"))
      (node (ref "D7") (pin "2") (pinfunction "A_2") (pintype "passive"))
      (node (ref "J1") (pin "1") (pinfunction "1_1") (pintype "bidirectional"))
      (node (ref "Q1") (pin "2") (pinfunction "S_2") (pintype "passive"))
      (node (ref "Q2") (pin "3") (pinfunction "D_3") (pintype "passive"))
      (node (ref "R1") (pin "1") (pinfunction "1_1") (pintype "passive"))
      (node (ref "R6") (pin "1") (pinfunction "1_1") (pintype "passive"))
      (node (ref "R7") (pin "2") (pinfunction "2_2") (pintype "passive"))
      (node (ref "U1") (pin "4") (pinfunction "V-_4") (pintype "power_in"))
      (node (ref "U1") (pin "5") (pinfunction "IN+_5") (pintype "input"))
      (node (ref "U1") (pin "6") (pinfunction "IN-_6") (pintype "input"))
    )
    (net (code "3") (name "/COM2") (class "Default")
      (node (ref "C6") (pin "2") (pinfunction "2_2") (pintype "passive"))
      (node (ref "D1") (pin "2") (pinfunction "A_2") (pintype "passive"))
      (node (ref "D9") (pin "2") (pinfunction "A_2") (pintype "passive"))
      (node (ref "J3") (pin "1") (pinfunction "1_1") (pintype "bidirectional"))
      (node (ref "Q5") (pin "2") (pinfunction "S_2") (pintype "passive"))
      (node (ref "Q6") (pin "3") (pinfunction "D_3") (pintype "passive"))
      (node (ref "R17") (pin "1") (pinfunction "1_1") (pintype "passive"))
      (node (ref "R22") (pin "1") (pinfunction "1_1") (pintype "passive"))
      (node (ref "R23") (pin "2") (pinfunction "2_2") (pintype "passive"))
      (node (ref "U2") (pin "4") (pinfunction "V-_4") (pintype "power_in"))
      (node (ref "U2") (pin "5") (pinfunction "IN+_5") (pintype "input"))
      (node (ref "U2") (pin "6") (pinfunction "IN-_6") (pintype "input"))
    )
    (net (code "4") (name "/COM3") (class "Default")
      (node (ref "C10") (pin "1") (pinfunction "1_1") (pintype "passive"))
      (node (ref "C15") (pin "2") (pinfunction "2_2") (pintype "passive"))
      (node (ref "C16") (pin "1") (pinfunction "1_1") (pintype "passive"))
      (node (ref "C2") (pin "1") (pinfunction "1_1") (pintype "passive"))
      (node (ref "C9") (pin "2") (pinfunction "2_2") (pintype "passive"))
      (node (ref "D10") (pin "2") (pinfunction "A_2") (pintype "passive"))
      (node (ref "D14") (pin "2") (pinfunction "A_2") (pintype "passive"))
      (node (ref "D4") (pin "2") (pinfunction "A_2") (pintype "passive"))
      (node (ref "J10") (pin "1") (pinfunction "1_1") (pintype "bidirectional"))
      (node (ref "Q2") (pin "2") (pinfunction "S_2") (pintype "passive"))
      (node (ref "Q3") (pin "3") (pinfunction "D_3") (pintype "passive"))
      (node (ref "Q6") (pin "2") (pinfunction "S_2") (pintype "passive"))
      (node (ref "Q7") (pin "3") (pinfunction "D_3") (pintype "passive"))
      (node (ref "R18") (pin "1") (pinfunction "1_1") (pintype "passive"))
      (node (ref "R2") (pin "1") (pinfunction "1_1") (pintype "passive"))
      (node (ref "R24") (pin "1") (pinfunction "1_1") (pintype "passive"))
      (node (ref "R25") (pin "2") (pinfunction "2_2") (pintype "passive"))
      (node (ref "R35") (pin "2") (pinfunction "2_2") (pintype "passive"))
      (node (ref "R36") (pin "1") (pinfunction "1_1") (pintype "passive"))
      (node (ref "R8") (pin "1") (pinfunction "1_1") (pintype "passive"))
      (node (ref "R9") (pin "2") (pinfunction "2_2") (pintype "passive"))
      (node (ref "U3") (pin "4") (pinfunction "V-_4") (pintype "power_in"))
    )
    (net (code "5") (name "/COM4") (class "Default")
      (node (ref "C3") (pin "2") (pinfunction "2_2") (pintype "passive"))
      (node (ref "D5") (pin "2") (pinfunction "A_2") (pintype "passive"))
      (node (ref "D8") (pin "2") (pinfunction "A_2") (pintype "passive"))
      (node (ref "J4") (pin "1") (pinfunction "1_1") (pintype "bidirectional"))
      (node (ref "Q3") (pin "2") (pinfunction "S_2") (pintype "passive"))
      (node (ref "Q4") (pin "3") (pinfunction "D_3") (pintype "passive"))
      (node (ref "R10") (pin "1") (pinfunction "1_1") (pintype "passive"))
      (node (ref "R11") (pin "2") (pinfunction "2_2") (pintype "passive"))
      (node (ref "R3") (pin "1") (pinfunction "1_1") (pintype "passive"))
      (node (ref "U4") (pin "4") (pinfunction "V-_4") (pintype "power_in"))
      (node (ref "U4") (pin "5") (pinfunction "IN+_5") (pintype "input"))
      (node (ref "U4") (pin "6") (pinfunction "IN-_6") (pintype "input"))
    )
    (net (code "6") (name "/COM5") (class "Default")
      (node (ref "C7") (pin "2") (pinfunction "2_2") (pintype "passive"))
      (node (ref "D11") (pin "2") (pinfunction "A_2") (pintype "passive"))
      (node (ref "D2") (pin "2") (pinfunction "A_2") (pintype "passive"))
      (node (ref "J6") (pin "1") (pinfunction "1_1") (pintype "bidirectional"))
      (node (ref "Q7") (pin "2") (pinfunction "S_2") (pintype "passive"))
      (node (ref "Q8") (pin "3") (pinfunction "D_3") (pintype "passive"))
      (node (ref "R19") (pin "1") (pinfunction "1_1") (pintype "passive"))
      (node (ref "R26") (pin "1") (pinfunction "1_1") (pintype "passive"))
      (node (ref "R27") (pin "2") (pinfunction "2_2") (pintype "passive"))
      (node (ref "U5") (pin "4") (pinfunction "V-_4") (pintype "power_in"))
      (node (ref "U5") (pin "5") (pinfunction "IN+_5") (pintype "input"))
      (node (ref "U5") (pin "6") (pinfunction "IN-_6") (pintype "input"))
    )
    (net (code "7") (name "/V1") (class "Default")
      (node (ref "C10") (pin "2") (pinfunction "2_2") (pintype "passive"))
      (node (ref "C11") (pin "1") (pinfunction "1_1") (pintype "passive"))
      (node (ref "C16") (pin "2") (pinfunction "2_2") (pintype "passive"))
      (node (ref "C17") (pin "1") (pinfunction "1_1") (pintype "passive"))
      (node (ref "J11") (pin "1") (pinfunction "1_1") (pintype "bidirectional"))
      (node (ref "J5") (pin "1") (pinfunction "1_1") (pintype "bidirectional"))
      (node (ref "R35") (pin "1") (pinfunction "1_1") (pintype "passive"))
      (node (ref "R37") (pin "2") (pinfunction "2_2") (pintype "passive"))
    )
    (net (code "8") (name "/V3") (class "Default")
      (node (ref "C14") (pin "2") (pinfunction "2_2") (pintype "passive"))
      (node (ref "C15") (pin "1") (pinfunction "1_1") (pintype "passive"))
      (node (ref "C8") (pin "2") (pinfunction "2_2") (pintype "passive"))
      (node (ref "C9") (pin "1") (pinfunction "1_1") (pintype "passive"))
      (node (ref "D15") (pin "2") (pinfunction "A_2") (pintype "passive"))
      (node (ref "J2") (pin "1") (pinfunction "1_1") (pintype "bidirectional"))
      (node (ref "J9") (pin "1") (pinfunction "1_1") (pintype "bidirectional"))
      (node (ref "R34") (pin "1") (pinfunction "1_1") (pintype "passive"))
      (node (ref "R36") (pin "2") (pinfunction "2_2") (pintype "passive"))
    )
    (net (code "9") (name "/V4") (class "Default")
      (node (ref "C12") (pin "2") (pinfunction "2_2") (pintype "passive"))
      (node (ref "C13") (pin "2") (pinfunction "2_2") (pintype "passive"))
      (node (ref "C14") (pin "1") (pinfunction "1_1") (pintype "passive"))
      (node (ref "C8") (pin "1") (pinfunction "1_1") (pintype "passive"))
      (node (ref "D13") (pin "2") (pinfunction "A_2") (pintype "passive"))
      (node (ref "J8") (pin "1") (pinfunction "1_1") (pintype "bidirectional"))
      (node (ref "Q1") (pin "3") (pinfunction "D_3") (pintype "passive"))
      (node (ref "Q5") (pin "3") (pinfunction "D_3") (pintype "passive"))
      (node (ref "R21") (pin "2") (pinfunction "2_2") (pintype "passive"))
      (node (ref "R33") (pin "1") (pinfunction "1_1") (pintype "passive"))
      (node (ref "R34") (pin "2") (pinfunction "2_2") (pintype "passive"))
      (node (ref "R5") (pin "2") (pinfunction "2_2") (pintype "passive"))
    )
    (net (code "10") (name "/VGATE") (class "Default")
      (node (ref "C12") (pin "1") (pinfunction "1_1") (pintype "passive"))
      (node (ref "C13") (pin "1") (pinfunction "1_1") (pintype "passive"))
      (node (ref "D16") (pin "1") (pinfunction "C_1") (pintype "passive"))
      (node (ref "J7") (pin "1") (pinfunction "1_1") (pintype "bidirectional"))
      (node (ref "R33") (pin "2") (pinfunction "2_2") (pintype "passive"))
    )
    (net (code "11") (name "Net-(D1-C)") (class "Default")
      (node (ref "C1") (pin "1") (pinfunction "1_1") (pintype "passive"))
      (node (ref "D1") (pin "1") (pinfunction "C_1") (pintype "passive"))
      (node (ref "R13") (pin "2") (pinfunction "2_2") (pintype "passive"))
      (node (ref "U1") (pin "8") (pinfunction "V+_8") (pintype "power_in"))
    )
    (net (code "12") (name "Net-(D2-C)") (class "Default")
      (node (ref "C3") (pin "1") (pinfunction "1_1") (pintype "passive"))
      (node (ref "D2") (pin "1") (pinfunction "C_1") (pintype "passive"))
      (node (ref "R15") (pin "2") (pinfunction "2_2") (pintype "passive"))
      (node (ref "U4") (pin "8") (pinfunction "V+_8") (pintype "power_in"))
    )
    (net (code "13") (name "Net-(D3-C)") (class "Default")
      (node (ref "D3") (pin "1") (pinfunction "C_1") (pintype "passive"))
      (node (ref "Q1") (pin "1") (pinfunction "G_1") (pintype "passive"))
      (node (ref "R13") (pin "1") (pinfunction "1_1") (pintype "passive"))
      (node (ref "U1") (pin "1") (pinfunction "OUT_1") (pintype "output"))
    )
    (net (code "14") (name "Net-(D4-C)") (class "Default")
      (node (ref "D4") (pin "1") (pinfunction "C_1") (pintype "passive"))
      (node (ref "Q2") (pin "1") (pinfunction "G_1") (pintype "passive"))
      (node (ref "R14") (pin "1") (pinfunction "1_1") (pintype "passive"))
      (node (ref "U3") (pin "1") (pinfunction "OUT_1") (pintype "output"))
    )
    (net (code "15") (name "Net-(D5-C)") (class "Default")
      (node (ref "D5") (pin "1") (pinfunction "C_1") (pintype "passive"))
      (node (ref "Q3") (pin "1") (pinfunction "G_1") (pintype "passive"))
      (node (ref "R15") (pin "1") (pinfunction "1_1") (pintype "passive"))
      (node (ref "U4") (pin "1") (pinfunction "OUT_1") (pintype "output"))
    )
    (net (code "16") (name "Net-(D6-C)") (class "Default")
      (node (ref "D6") (pin "1") (pinfunction "C_1") (pintype "passive"))
      (node (ref "Q4") (pin "1") (pinfunction "G_1") (pintype "passive"))
      (node (ref "R16") (pin "1") (pinfunction "1_1") (pintype "passive"))
      (node (ref "U6") (pin "1") (pinfunction "OUT_1") (pintype "output"))
    )
    (net (code "17") (name "Net-(D7-C)") (class "Default")
      (node (ref "C6") (pin "1") (pinfunction "1_1") (pintype "passive"))
      (node (ref "D7") (pin "1") (pinfunction "C_1") (pintype "passive"))
      (node (ref "R29") (pin "2") (pinfunction "2_2") (pintype "passive"))
      (node (ref "U2") (pin "8") (pinfunction "V+_8") (pintype "power_in"))
    )
    (net (code "18") (name "Net-(D8-C)") (class "Default")
      (node (ref "C7") (pin "1") (pinfunction "1_1") (pintype "passive"))
      (node (ref "D8") (pin "1") (pinfunction "C_1") (pintype "passive"))
      (node (ref "R31") (pin "2") (pinfunction "2_2") (pintype "passive"))
      (node (ref "U5") (pin "8") (pinfunction "V+_8") (pintype "power_in"))
    )
    (net (code "19") (name "Net-(D9-C)") (class "Default")
      (node (ref "D9") (pin "1") (pinfunction "C_1") (pintype "passive"))
      (node (ref "Q5") (pin "1") (pinfunction "G_1") (pintype "passive"))
      (node (ref "R29") (pin "1") (pinfunction "1_1") (pintype "passive"))
      (node (ref "U2") (pin "1") (pinfunction "OUT_1") (pintype "output"))
    )
    (net (code "20") (name "Net-(D10-C)") (class "Default")
      (node (ref "D10") (pin "1") (pinfunction "C_1") (pintype "passive"))
      (node (ref "Q6") (pin "1") (pinfunction "G_1") (pintype "passive"))
      (node (ref "R30") (pin "1") (pinfunction "1_1") (pintype "passive"))
      (node (ref "U3") (pin "7") (pinfunction "OUT_7") (pintype "output"))
    )
    (net (code "21") (name "Net-(D11-C)") (class "Default")
      (node (ref "D11") (pin "1") (pinfunction "C_1") (pintype "passive"))
      (node (ref "Q7") (pin "1") (pinfunction "G_1") (pintype "passive"))
      (node (ref "R31") (pin "1") (pinfunction "1_1") (pintype "passive"))
      (node (ref "U5") (pin "1") (pinfunction "OUT_1") (pintype "output"))
    )
    (net (code "22") (name "Net-(D12-C)") (class "Default")
      (node (ref "D12") (pin "1") (pinfunction "C_1") (pintype "passive"))
      (node (ref "Q8") (pin "1") (pinfunction "G_1") (pintype "passive"))
      (node (ref "R32") (pin "1") (pinfunction "1_1") (pintype "passive"))
      (node (ref "U6") (pin "7") (pinfunction "OUT_7") (pintype "output"))
    )
    (net (code "23") (name "Net-(D13-C)") (class "Default")
      (node (ref "C2") (pin "2") (pinfunction "2_2") (pintype "passive"))
      (node (ref "D13") (pin "1") (pinfunction "C_1") (pintype "passive"))
      (node (ref "R14") (pin "2") (pinfunction "2_2") (pintype "passive"))
      (node (ref "R30") (pin "2") (pinfunction "2_2") (pintype "passive"))
      (node (ref "U3") (pin "8") (pinfunction "V+_8") (pintype "power_in"))
    )
    (net (code "24") (name "Net-(D14-C)") (class "Default")
      (node (ref "C4") (pin "2") (pinfunction "2_2") (pintype "passive"))
      (node (ref "D14") (pin "1") (pinfunction "C_1") (pintype "passive"))
      (node (ref "R16") (pin "2") (pinfunction "2_2") (pintype "passive"))
      (node (ref "R32") (pin "2") (pinfunction "2_2") (pintype "passive"))
      (node (ref "U6") (pin "8") (pinfunction "V+_8") (pintype "power_in"))
    )
    (net (code "25") (name "Net-(D15-C)") (class "Default")
      (node (ref "C5") (pin "1") (pinfunction "1_1") (pintype "passive"))
      (node (ref "D15") (pin "1") (pinfunction "C_1") (pintype "passive"))
      (node (ref "D16") (pin "2") (pinfunction "A_2") (pintype "passive"))
    )
    (net (code "26") (name "Net-(U1A-IN+)") (class "Default")
      (node (ref "R1") (pin "2") (pinfunction "2_2") (pintype "passive"))
      (node (ref "U1") (pin "3") (pinfunction "IN+_3") (pintype "input"))
    )
    (net (code "27") (name "Net-(U1A-IN-)") (class "Default")
      (node (ref "R5") (pin "1") (pinfunction "1_1") (pintype "passive"))
      (node (ref "R6") (pin "2") (pinfunction "2_2") (pintype "passive"))
      (node (ref "U1") (pin "2") (pinfunction "IN-_2") (pintype "input"))
    )
    (net (code "28") (name "Net-(U2A-IN+)") (class "Default")
      (node (ref "R17") (pin "2") (pinfunction "2_2") (pintype "passive"))
      (node (ref "U2") (pin "3") (pinfunction "IN+_3") (pintype "input"))
    )
    (net (code "29") (name "Net-(U2A-IN-)") (class "Default")
      (node (ref "R21") (pin "1") (pinfunction "1_1") (pintype "passive"))
      (node (ref "R22") (pin "2") (pinfunction "2_2") (pintype "passive"))
      (node (ref "U2") (pin "2") (pinfunction "IN-_2") (pintype "input"))
    )
    (net (code "30") (name "Net-(U3A-IN+)") (class "Default")
      (node (ref "R2") (pin "2") (pinfunction "2_2") (pintype "passive"))
      (node (ref "U3") (pin "3") (pinfunction "IN+_3") (pintype "input"))
    )
    (net (code "31") (name "Net-(U3A-IN-)") (class "Default")
      (node (ref "R7") (pin "1") (pinfunction "1_1") (pintype "passive"))
      (node (ref "R8") (pin "2") (pinfunction "2_2") (pintype "passive"))
      (node (ref "U3") (pin "2") (pinfunction "IN-_2") (pintype "input"))
    )
    (net (code "32") (name "Net-(U3B-IN+)") (class "Default")
      (node (ref "R18") (pin "2") (pinfunction "2_2") (pintype "passive"))
      (node (ref "U3") (pin "5") (pinfunction "IN+_5") (pintype "input"))
    )
    (net (code "33") (name "Net-(U3B-IN-)") (class "Default")
      (node (ref "R23") (pin "1") (pinfunction "1_1") (pintype "passive"))
      (node (ref "R24") (pin "2") (pinfunction "2_2") (pintype "passive"))
      (node (ref "U3") (pin "6") (pinfunction "IN-_6") (pintype "input"))
    )
    (net (code "34") (name "Net-(U4A-IN+)") (class "Default")
      (node (ref "R3") (pin "2") (pinfunction "2_2") (pintype "passive"))
      (node (ref "U4") (pin "3") (pinfunction "IN+_3") (pintype "input"))
    )
    (net (code "35") (name "Net-(U4A-IN-)") (class "Default")
      (node (ref "R10") (pin "2") (pinfunction "2_2") (pintype "passive"))
      (node (ref "R9") (pin "1") (pinfunction "1_1") (pintype "passive"))
      (node (ref "U4") (pin "2") (pinfunction "IN-_2") (pintype "input"))
    )
    (net (code "36") (name "Net-(U5A-IN+)") (class "Default")
      (node (ref "R19") (pin "2") (pinfunction "2_2") (pintype "passive"))
      (node (ref "U5") (pin "3") (pinfunction "IN+_3") (pintype "input"))
    )
    (net (code "37") (name "Net-(U5A-IN-)") (class "Default")
      (node (ref "R25") (pin "1") (pinfunction "1_1") (pintype "passive"))
      (node (ref "R26") (pin "2") (pinfunction "2_2") (pintype "passive"))
      (node (ref "U5") (pin "2") (pinfunction "IN-_2") (pintype "input"))
    )
    (net (code "38") (name "Net-(U6A-IN+)") (class "Default")
      (node (ref "R4") (pin "2") (pinfunction "2_2") (pintype "passive"))
      (node (ref "U6") (pin "3") (pinfunction "IN+_3") (pintype "input"))
    )
    (net (code "39") (name "Net-(U6A-IN-)") (class "Default")
      (node (ref "R11") (pin "1") (pinfunction "1_1") (pintype "passive"))
      (node (ref "R12") (pin "2") (pinfunction "2_2") (pintype "passive"))
      (node (ref "U6") (pin "2") (pinfunction "IN-_2") (pintype "input"))
    )
    (net (code "40") (name "Net-(U6B-IN+)") (class "Default")
      (node (ref "R20") (pin "2") (pinfunction "2_2") (pintype "passive"))
      (node (ref "U6") (pin "5") (pinfunction "IN+_5") (pintype "input"))
    )
    (net (code "41") (name "Net-(U6B-IN-)") (class "Default")
      (node (ref "R27") (pin "1") (pinfunction "1_1") (pintype "passive"))
      (node (ref "R28") (pin "2") (pinfunction "2_2") (pintype "passive"))
      (node (ref "U6") (pin "6") (pinfunction "IN-_6") (pintype "input"))
    )
    (net (code "42") (name "unconnected-(U1B-OUT-Pad7)") (class "Default")
      (node (ref "U1") (pin "7") (pinfunction "OUT_7") (pintype "output"))
    )
    (net (code "43") (name "unconnected-(U2B-OUT-Pad7)") (class "Default")
      (node (ref "U2") (pin "7") (pinfunction "OUT_7") (pintype "output"))
    )
    (net (code "44") (name "unconnected-(U4B-OUT-Pad7)") (class "Default")
      (node (ref "U4") (pin "7") (pinfunction "OUT_7") (pintype "output"))
    )
    (net (code "45") (name "unconnected-(U5B-OUT-Pad7)") (class "Default")
      (node (ref "U5") (pin "7") (pinfunction "OUT_7") (pintype "output"))
    )
  )
)
